# RoverWingPogoBed-V1.net
KiCad netlist of a schematic drawn in EAGLE
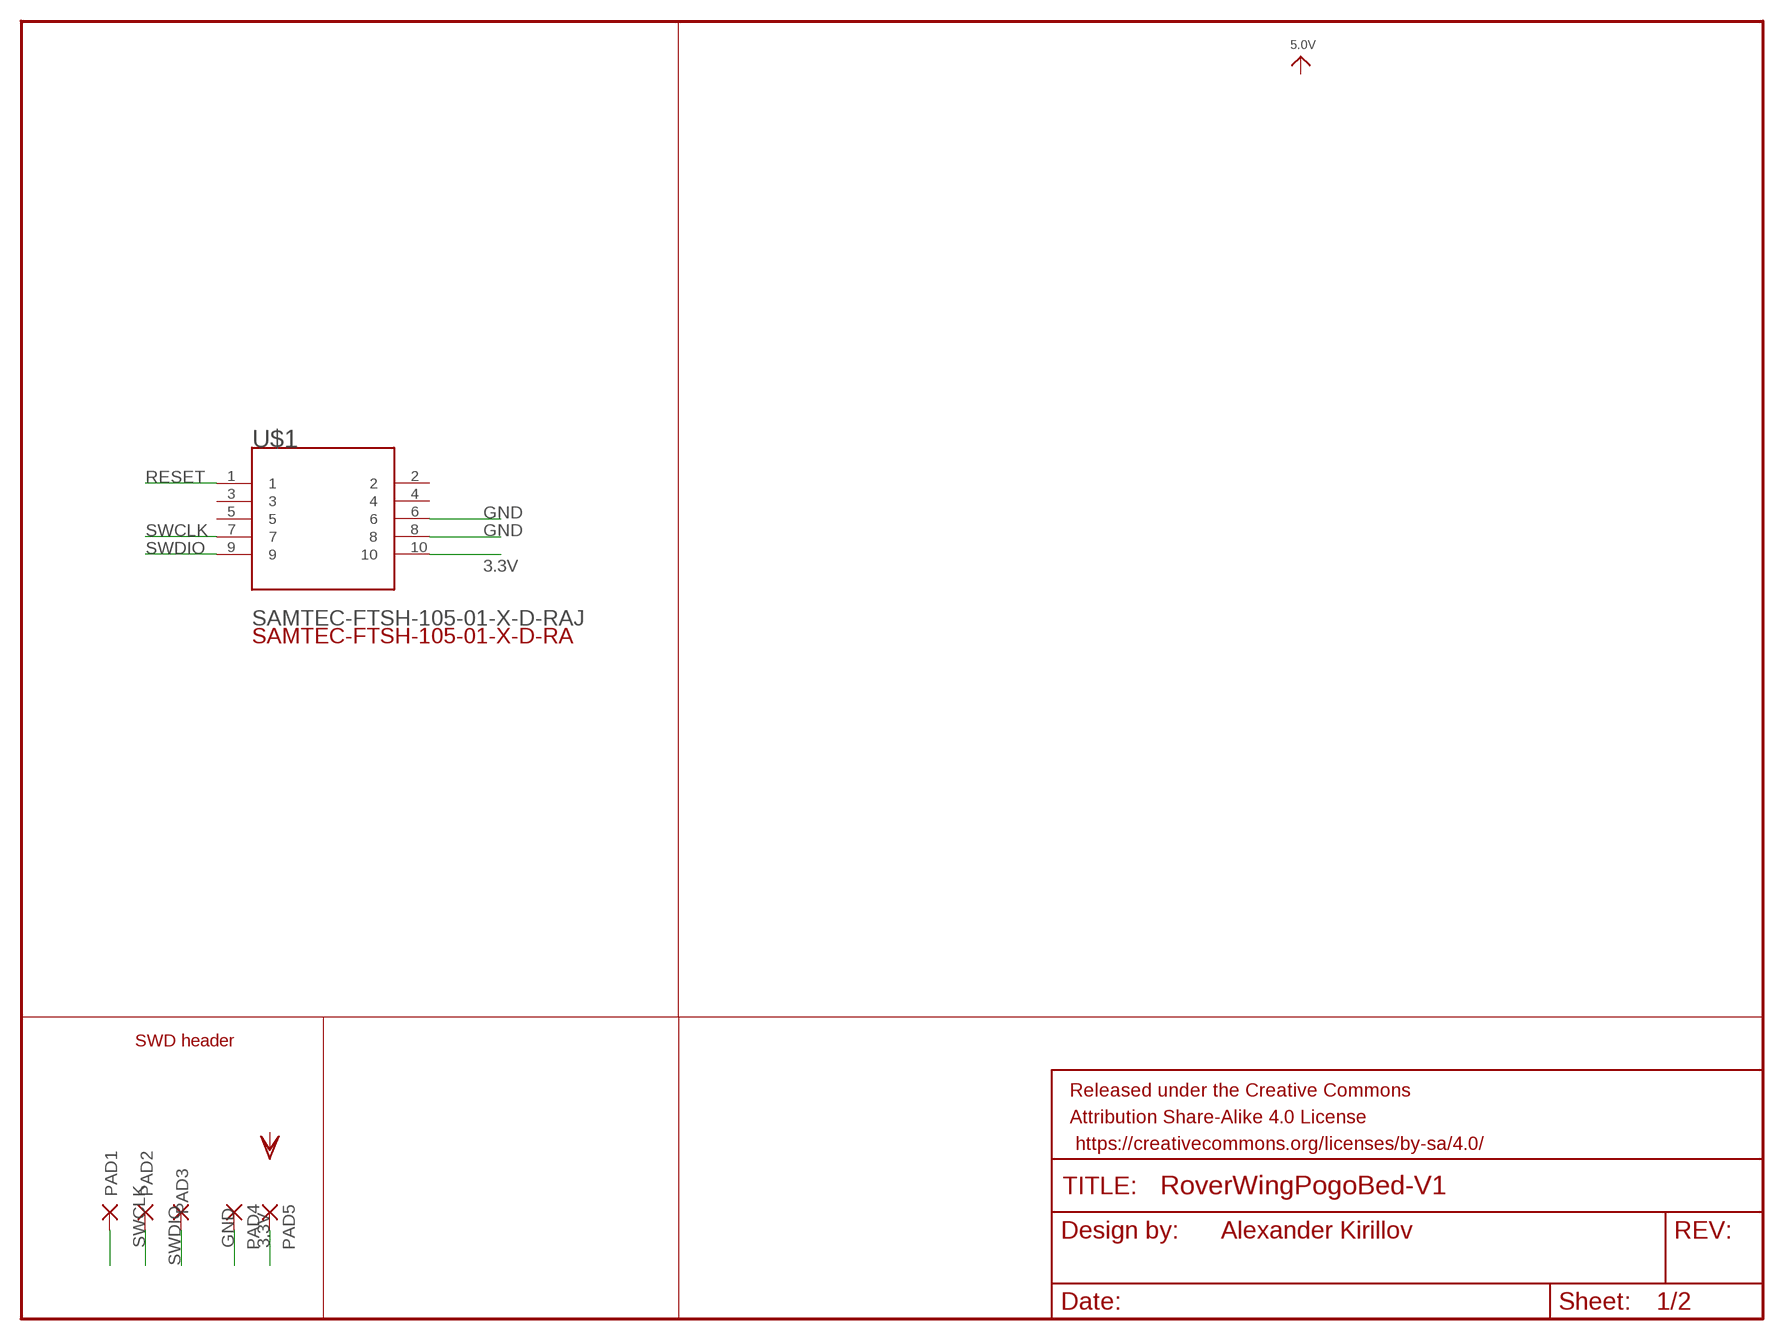
[diagram p0: schematic, sheet 1]
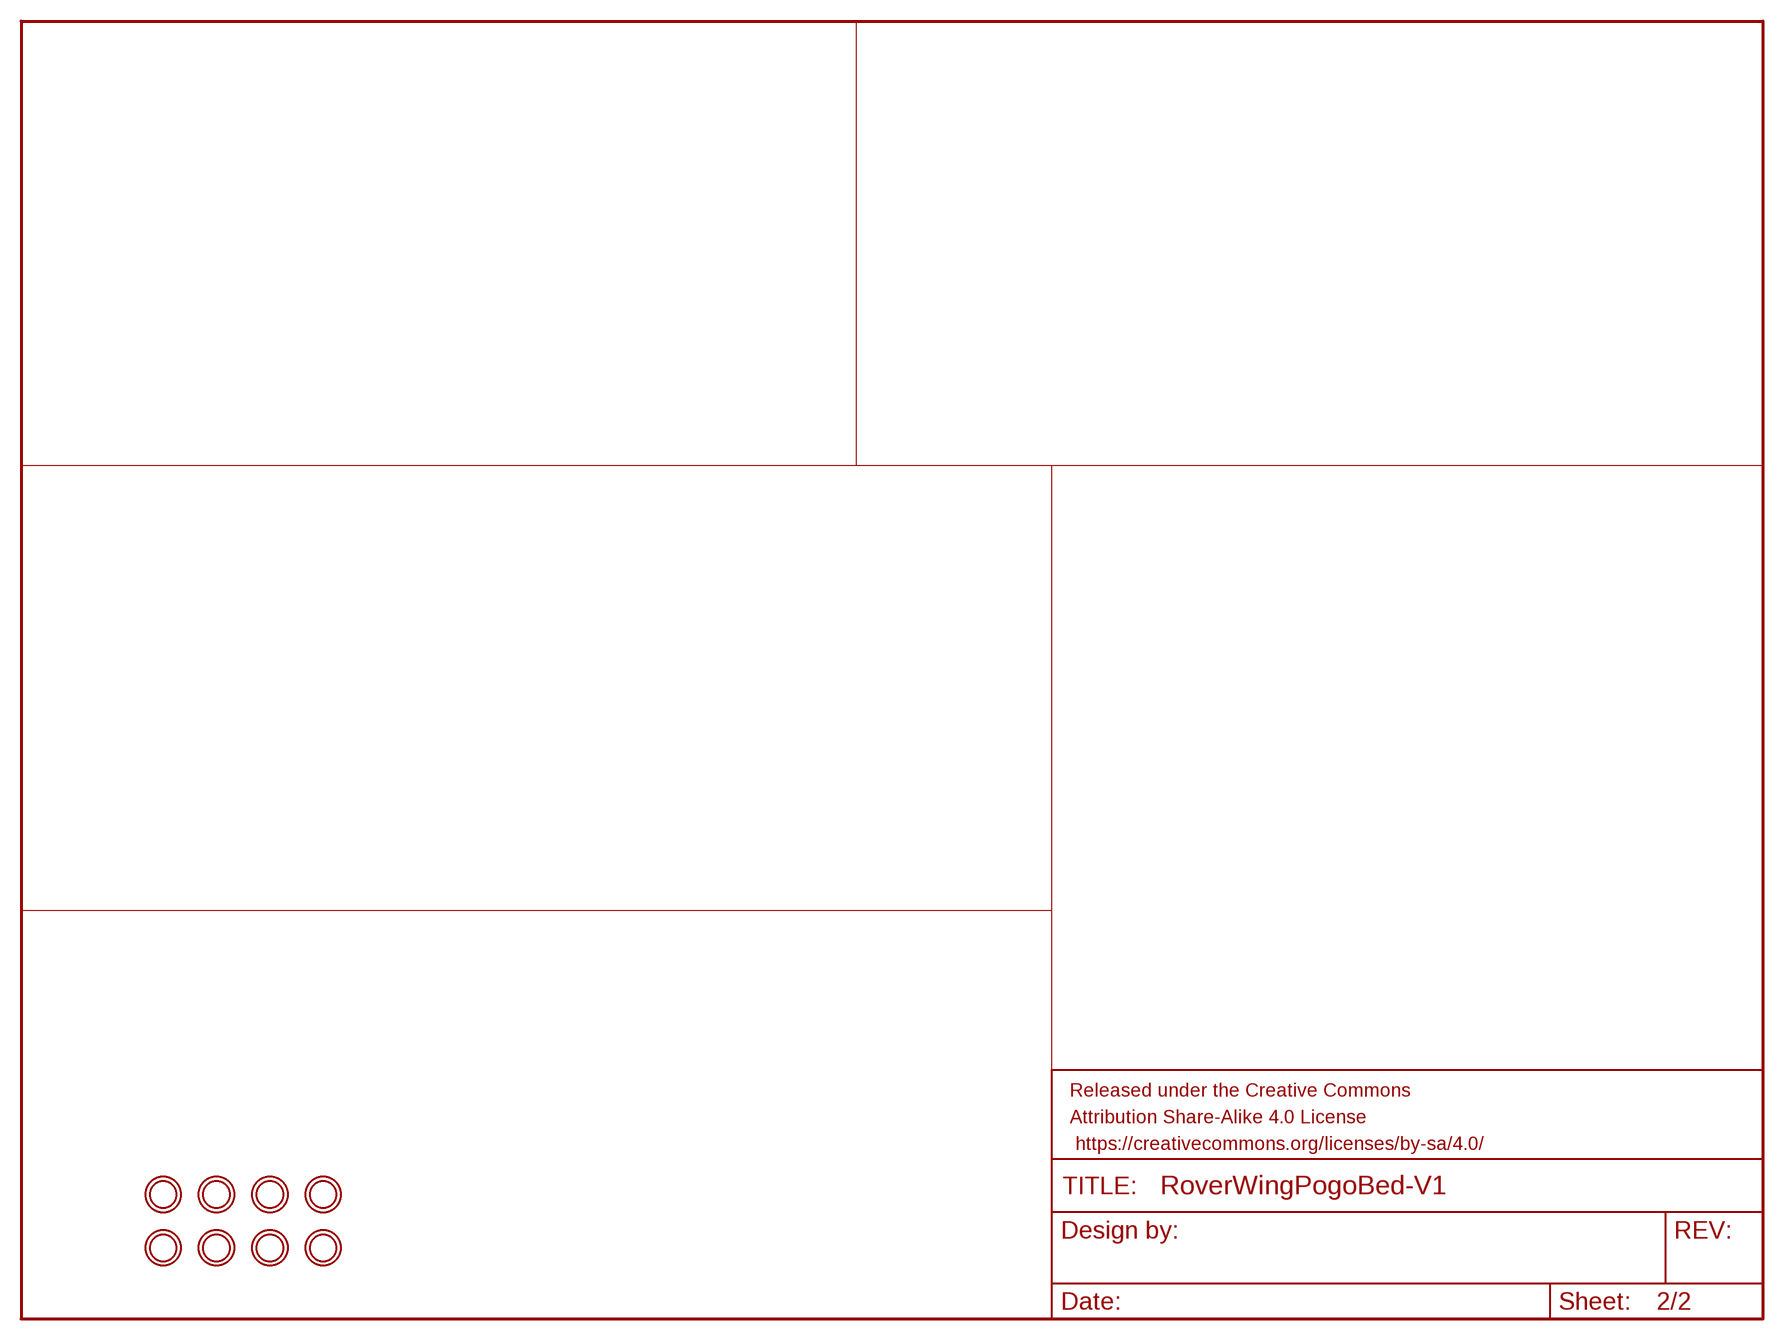
[diagram p1: schematic, sheet 2]

(export (version "E")
  (design (tool "Eeschema 10.0.6"))
  (components
    (comp (ref "FRAME1")
      (value "FRAME-LETTERNO_PACKAGE")
      (footprint "eagle-import:DUMMY")
      (fields (field (name "DESIGNER") "Nobody"))
      (libsource (lib "eagle-import") (part "FRAME-LETTERNO_PACKAGE"))
    )
    (comp (ref "U$3")
      (value "MOUNTINGHOLE3.0_NPH")
      (footprint "eagle-import:MOUNTINGHOLE_3.0_NPH")
      (libsource (lib "eagle-import") (part "MOUNTINGHOLE3.0_NPH"))
    )
    (comp (ref "U$4")
      (value "MOUNTINGHOLE3.0_NPH")
      (footprint "eagle-import:MOUNTINGHOLE_3.0_NPH")
      (libsource (lib "eagle-import") (part "MOUNTINGHOLE3.0_NPH"))
    )
    (comp (ref "U$14")
      (value "MOUNTINGHOLE3.0_NPH")
      (footprint "eagle-import:MOUNTINGHOLE_3.0_NPH")
      (libsource (lib "eagle-import") (part "MOUNTINGHOLE3.0_NPH"))
    )
    (comp (ref "U$15")
      (value "MOUNTINGHOLE3.0_NPH")
      (footprint "eagle-import:MOUNTINGHOLE_3.0_NPH")
      (libsource (lib "eagle-import") (part "MOUNTINGHOLE3.0_NPH"))
    )
    (comp (ref "U$24")
      (value "MOUNTINGHOLE3.0_NPH")
      (footprint "eagle-import:MOUNTINGHOLE_3.0_NPH")
      (libsource (lib "eagle-import") (part "MOUNTINGHOLE3.0_NPH"))
    )
    (comp (ref "U$25")
      (value "MOUNTINGHOLE3.0_NPH")
      (footprint "eagle-import:MOUNTINGHOLE_3.0_NPH")
      (libsource (lib "eagle-import") (part "MOUNTINGHOLE3.0_NPH"))
    )
    (comp (ref "U$26")
      (value "MOUNTINGHOLE3.0_NPH")
      (footprint "eagle-import:MOUNTINGHOLE_3.0_NPH")
      (libsource (lib "eagle-import") (part "MOUNTINGHOLE3.0_NPH"))
    )
    (comp (ref "U$27")
      (value "MOUNTINGHOLE3.0_NPH")
      (footprint "eagle-import:MOUNTINGHOLE_3.0_NPH")
      (libsource (lib "eagle-import") (part "MOUNTINGHOLE3.0_NPH"))
    )
    (comp (ref "FRAME2")
      (value "FRAME-LETTERNO_PACKAGE")
      (footprint "eagle-import:DUMMY")
      (fields (field (name "DESIGNER") "Nobody"))
      (libsource (lib "eagle-import") (part "FRAME-LETTERNO_PACKAGE"))
    )
    (comp (ref "PAD1")
      (value "2,15/1,0")
      (footprint "eagle-import:2,15_1,0")
      (libsource (lib "eagle-import") (part "2,15/1,0"))
    )
    (comp (ref "PAD2")
      (value "2,15/1,0")
      (footprint "eagle-import:2,15_1,0")
      (libsource (lib "eagle-import") (part "2,15/1,0"))
    )
    (comp (ref "PAD3")
      (value "2,15/1,0")
      (footprint "eagle-import:2,15_1,0")
      (libsource (lib "eagle-import") (part "2,15/1,0"))
    )
    (comp (ref "PAD4")
      (value "2,15/1,0")
      (footprint "eagle-import:2,15_1,0")
      (libsource (lib "eagle-import") (part "2,15/1,0"))
    )
    (comp (ref "PAD5")
      (value "2,15/1,0")
      (footprint "eagle-import:2,15_1,0")
      (libsource (lib "eagle-import") (part "2,15/1,0"))
    )
    (comp (ref "U$1")
      (value "SAMTEC-FTSH-105-01-X-D-RAJ")
      (footprint "eagle-import:SAMTEC-FTSH-105-01-X-D-RA")
      (fields
        (field (name "DIGI-KEY_PART_NUMBER") "SAM9432-ND")
        (field (name "MF") "Samtec Inc.")
        (field (name "MP") "FTSH-105-01-F-D-RA-K")
      )
      (libsource (lib "eagle-import") (part "SAMTEC-FTSH-105-01-X-D-RAJ"))
    )
  )
  (nets
    (net (code "1") (name "3.3V") (class "Default")
      (node (ref "PAD5") (pin "1") (pinfunction "P_1") (pintype "passive"))
      (node (ref "U$1") (pin "10") (pinfunction "10_10") (pintype "passive"))
    )
    (net (code "3") (name "GND") (class "Default")
      (node (ref "PAD4") (pin "1") (pinfunction "P_1") (pintype "passive"))
      (node (ref "U$1") (pin "6") (pinfunction "6_6") (pintype "passive"))
      (node (ref "U$1") (pin "8") (pinfunction "8_8") (pintype "passive"))
    )
    (net (code "4") (name "RESET") (class "Default")
      (node (ref "PAD1") (pin "1") (pinfunction "P_1") (pintype "passive"))
      (node (ref "U$1") (pin "1") (pinfunction "1_1") (pintype "passive"))
    )
    (net (code "5") (name "SWCLK") (class "Default")
      (node (ref "PAD2") (pin "1") (pinfunction "P_1") (pintype "passive"))
      (node (ref "U$1") (pin "7") (pinfunction "7_7") (pintype "passive"))
    )
    (net (code "6") (name "SWDIO") (class "Default")
      (node (ref "PAD3") (pin "1") (pinfunction "P_1") (pintype "passive"))
      (node (ref "U$1") (pin "9") (pinfunction "9_9") (pintype "passive"))
    )
    (net (code "8") (name "unconnected-(U$1-Pad2)") (class "Default")
      (node (ref "U$1") (pin "2") (pinfunction "2_2") (pintype "passive"))
    )
    (net (code "9") (name "unconnected-(U$1-Pad3)") (class "Default")
      (node (ref "U$1") (pin "3") (pinfunction "3_3") (pintype "passive"))
    )
    (net (code "10") (name "unconnected-(U$1-Pad4)") (class "Default")
      (node (ref "U$1") (pin "4") (pinfunction "4_4") (pintype "passive"))
    )
    (net (code "11") (name "unconnected-(U$1-Pad5)") (class "Default")
      (node (ref "U$1") (pin "5") (pinfunction "5_5") (pintype "passive"))
    )
  )
)
